# bpf_att.net
KiCad netlist of a schematic drawn in EAGLE
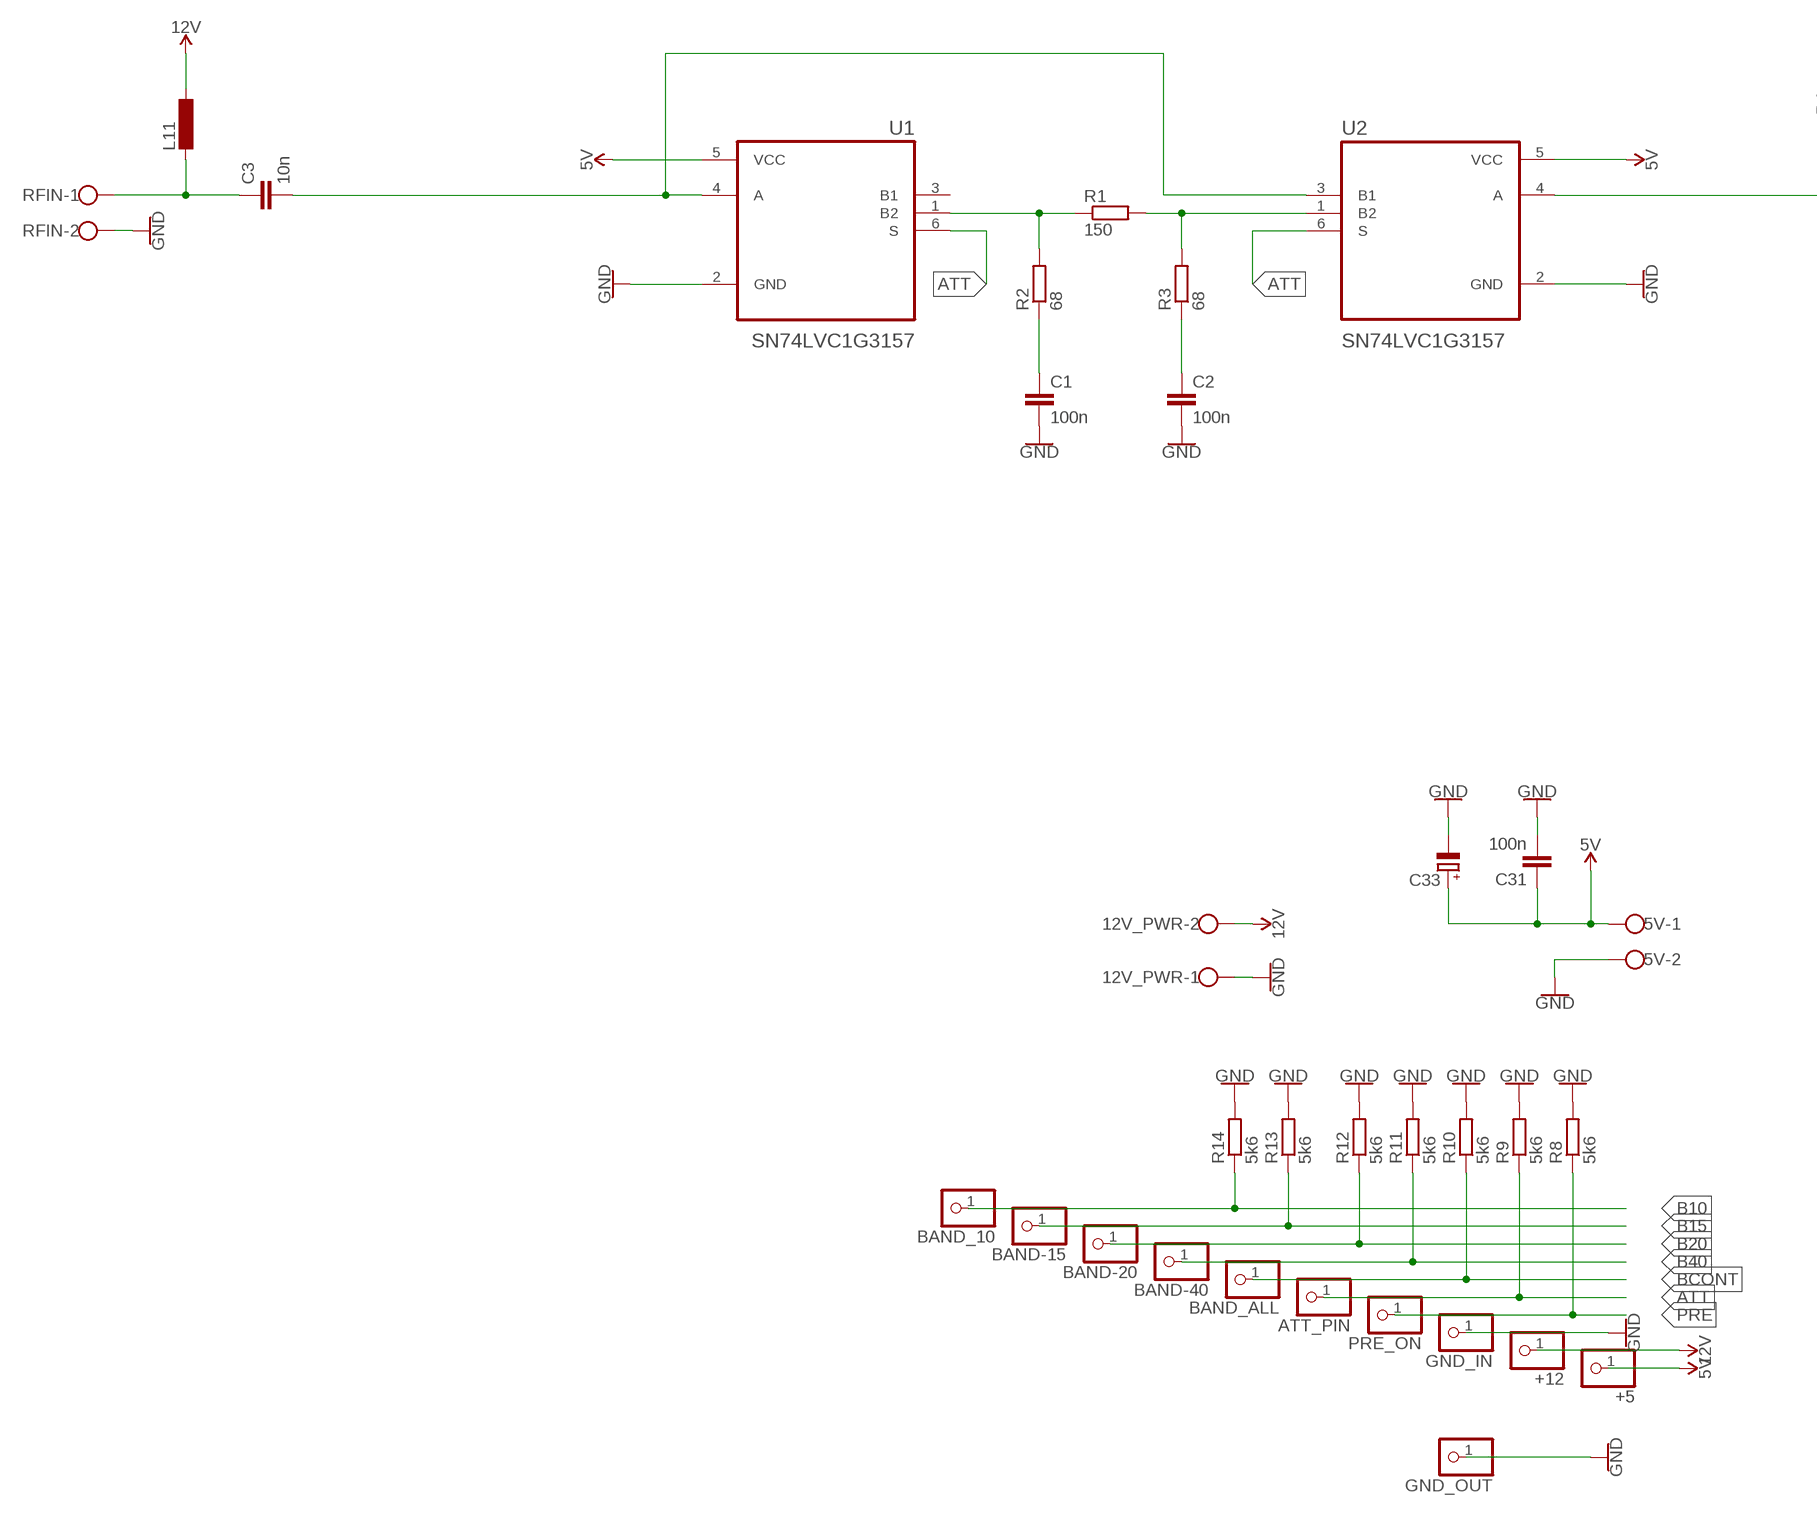
[diagram p0: schematic, sheet 1, part 1 of 2]
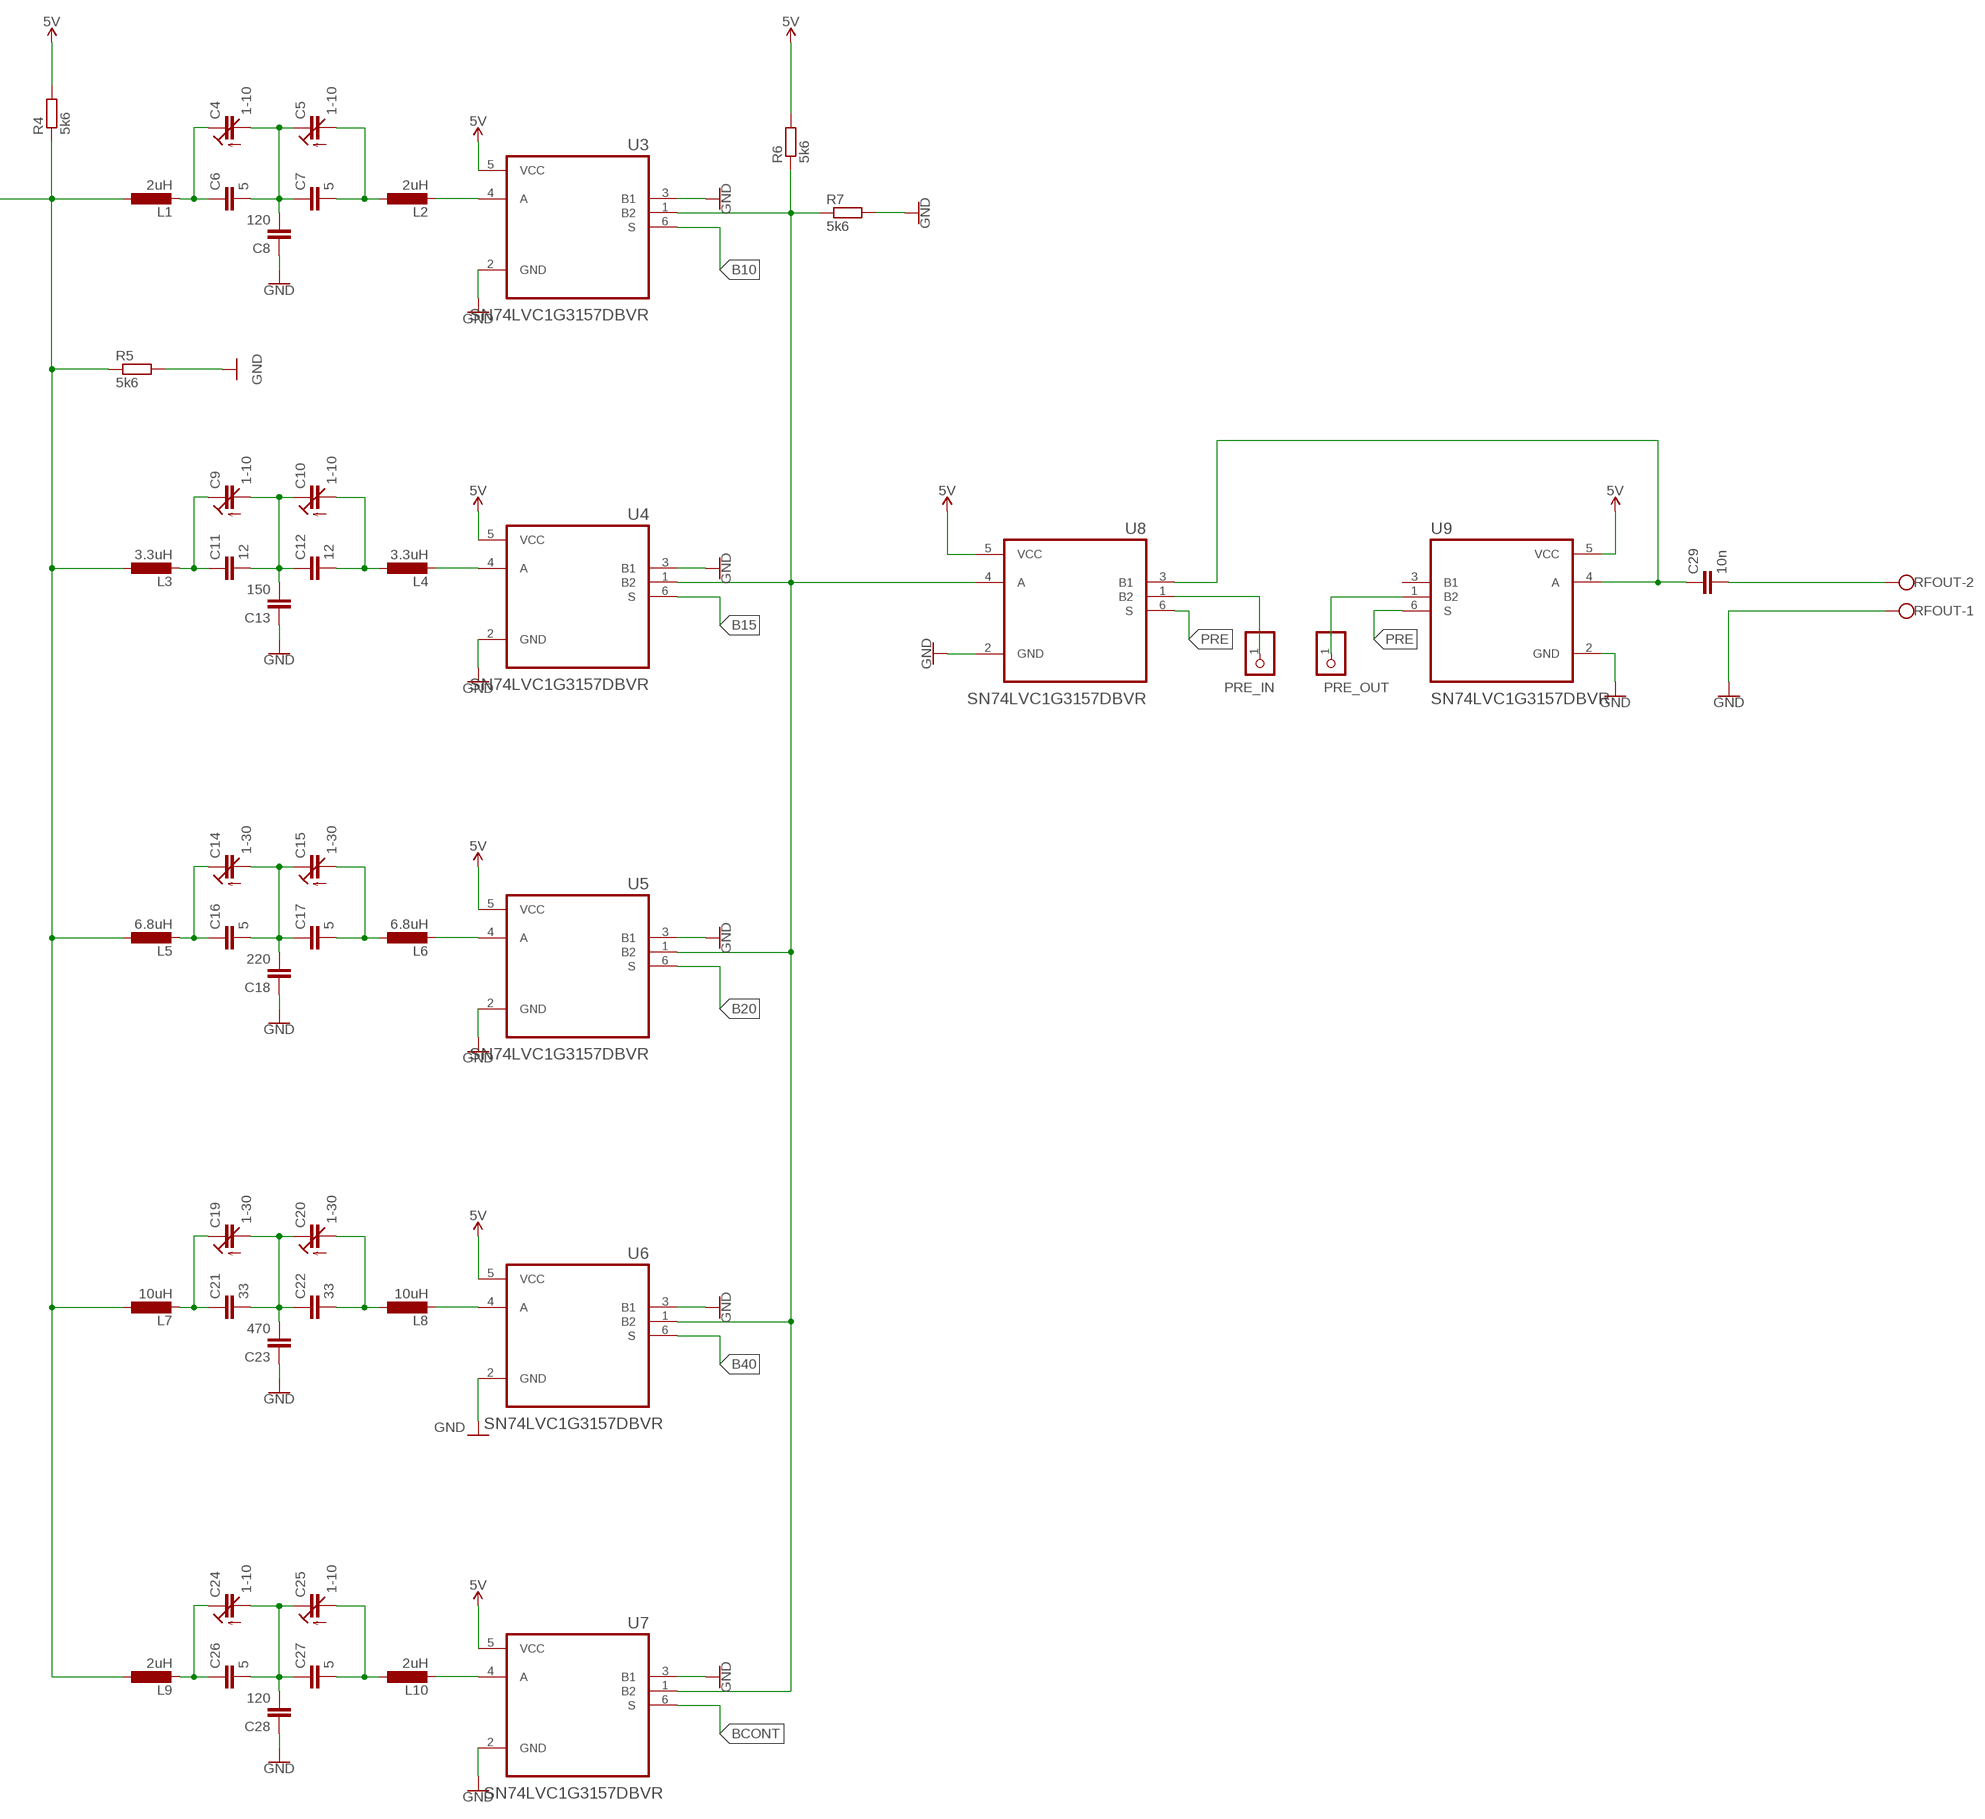
[diagram p1: schematic, sheet 1, part 2 of 2]

(export (version "E")
  (design (tool "Eeschema 10.0.6"))
  (components
    (comp (ref "+5")
      (value "PINHD-1X1")
      (footprint "eagle-import:1X01")
      (libsource (lib "eagle-import") (part "PINHD-1X1"))
    )
    (comp (ref "+12")
      (value "PINHD-1X1")
      (footprint "eagle-import:1X01")
      (libsource (lib "eagle-import") (part "PINHD-1X1"))
    )
    (comp (ref "5V")
      (value "W237-102")
      (footprint "eagle-import:W237-102")
      (fields (field (name "MPN") "237-102"))
      (libsource (lib "eagle-import") (part "W237-102"))
    )
    (comp (ref "12V_PWR")
      (value "W237-102")
      (footprint "eagle-import:W237-102")
      (fields (field (name "MPN") "237-102"))
      (libsource (lib "eagle-import") (part "W237-102"))
    )
    (comp (ref "ATT_PIN")
      (value "PINHD-1X1")
      (footprint "eagle-import:1X01")
      (libsource (lib "eagle-import") (part "PINHD-1X1"))
    )
    (comp (ref "BAND-15")
      (value "PINHD-1X1")
      (footprint "eagle-import:1X01")
      (libsource (lib "eagle-import") (part "PINHD-1X1"))
    )
    (comp (ref "BAND-20")
      (value "PINHD-1X1")
      (footprint "eagle-import:1X01")
      (libsource (lib "eagle-import") (part "PINHD-1X1"))
    )
    (comp (ref "BAND-40")
      (value "PINHD-1X1")
      (footprint "eagle-import:1X01")
      (libsource (lib "eagle-import") (part "PINHD-1X1"))
    )
    (comp (ref "BAND_10")
      (value "PINHD-1X1")
      (footprint "eagle-import:1X01")
      (libsource (lib "eagle-import") (part "PINHD-1X1"))
    )
    (comp (ref "BAND_ALL")
      (value "PINHD-1X1")
      (footprint "eagle-import:1X01")
      (libsource (lib "eagle-import") (part "PINHD-1X1"))
    )
    (comp (ref "C1")
      (value "100n")
      (footprint "eagle-import:C1206")
      (libsource (lib "eagle-import") (part "C-EUC1206"))
    )
    (comp (ref "C2")
      (value "100n")
      (footprint "eagle-import:C1206")
      (libsource (lib "eagle-import") (part "C-EUC1206"))
    )
    (comp (ref "C3")
      (value "10n")
      (footprint "eagle-import:C1206K")
      (libsource (lib "eagle-import") (part "C-EUC1206K"))
    )
    (comp (ref "C4")
      (value "1-10")
      (footprint "eagle-import:CTRIM3050.504")
      (libsource (lib "eagle-import") (part "C-TRIMM3050.504"))
    )
    (comp (ref "C5")
      (value "1-10")
      (footprint "eagle-import:CTRIM3050.504")
      (libsource (lib "eagle-import") (part "C-TRIMM3050.504"))
    )
    (comp (ref "C6")
      (value "5")
      (footprint "eagle-import:C1206K")
      (libsource (lib "eagle-import") (part "C-EUC1206K"))
    )
    (comp (ref "C7")
      (value "5")
      (footprint "eagle-import:C1206K")
      (libsource (lib "eagle-import") (part "C-EUC1206K"))
    )
    (comp (ref "C8")
      (value "120")
      (footprint "eagle-import:C1206K")
      (libsource (lib "eagle-import") (part "C-EUC1206K"))
    )
    (comp (ref "C9")
      (value "1-10")
      (footprint "eagle-import:CTRIM3050.504")
      (libsource (lib "eagle-import") (part "C-TRIMM3050.504"))
    )
    (comp (ref "C10")
      (value "1-10")
      (footprint "eagle-import:CTRIM3050.504")
      (libsource (lib "eagle-import") (part "C-TRIMM3050.504"))
    )
    (comp (ref "C11")
      (value "12")
      (footprint "eagle-import:C1206K")
      (libsource (lib "eagle-import") (part "C-EUC1206K"))
    )
    (comp (ref "C12")
      (value "12")
      (footprint "eagle-import:C1206K")
      (libsource (lib "eagle-import") (part "C-EUC1206K"))
    )
    (comp (ref "C13")
      (value "150")
      (footprint "eagle-import:C1206K")
      (libsource (lib "eagle-import") (part "C-EUC1206K"))
    )
    (comp (ref "C14")
      (value "1-30")
      (footprint "eagle-import:CTRIM3050.504")
      (libsource (lib "eagle-import") (part "C-TRIMM3050.504"))
    )
    (comp (ref "C15")
      (value "1-30")
      (footprint "eagle-import:CTRIM3050.504")
      (libsource (lib "eagle-import") (part "C-TRIMM3050.504"))
    )
    (comp (ref "C16")
      (value "5")
      (footprint "eagle-import:C1206K")
      (libsource (lib "eagle-import") (part "C-EUC1206K"))
    )
    (comp (ref "C17")
      (value "5")
      (footprint "eagle-import:C1206K")
      (libsource (lib "eagle-import") (part "C-EUC1206K"))
    )
    (comp (ref "C18")
      (value "220")
      (footprint "eagle-import:C1206K")
      (libsource (lib "eagle-import") (part "C-EUC1206K"))
    )
    (comp (ref "C19")
      (value "1-30")
      (footprint "eagle-import:CTRIM3050.504")
      (libsource (lib "eagle-import") (part "C-TRIMM3050.504"))
    )
    (comp (ref "C20")
      (value "1-30")
      (footprint "eagle-import:CTRIM3050.504")
      (libsource (lib "eagle-import") (part "C-TRIMM3050.504"))
    )
    (comp (ref "C21")
      (value "33")
      (footprint "eagle-import:C1206K")
      (libsource (lib "eagle-import") (part "C-EUC1206K"))
    )
    (comp (ref "C22")
      (value "33")
      (footprint "eagle-import:C1206K")
      (libsource (lib "eagle-import") (part "C-EUC1206K"))
    )
    (comp (ref "C23")
      (value "470")
      (footprint "eagle-import:C1206K")
      (libsource (lib "eagle-import") (part "C-EUC1206K"))
    )
    (comp (ref "C24")
      (value "1-10")
      (footprint "eagle-import:CTRIM3050.504")
      (libsource (lib "eagle-import") (part "C-TRIMM3050.504"))
    )
    (comp (ref "C25")
      (value "1-10")
      (footprint "eagle-import:CTRIM3050.504")
      (libsource (lib "eagle-import") (part "C-TRIMM3050.504"))
    )
    (comp (ref "C26")
      (value "5")
      (footprint "eagle-import:C1206K")
      (libsource (lib "eagle-import") (part "C-EUC1206K"))
    )
    (comp (ref "C27")
      (value "5")
      (footprint "eagle-import:C1206K")
      (libsource (lib "eagle-import") (part "C-EUC1206K"))
    )
    (comp (ref "C28")
      (value "120")
      (footprint "eagle-import:C1206K")
      (libsource (lib "eagle-import") (part "C-EUC1206K"))
    )
    (comp (ref "C29")
      (value "10n")
      (footprint "eagle-import:C1206K")
      (libsource (lib "eagle-import") (part "C-EUC1206K"))
    )
    (comp (ref "C31")
      (value "100n")
      (footprint "eagle-import:C1206")
      (libsource (lib "eagle-import") (part "C-EUC1206"))
    )
    (comp (ref "C33")
      (value "CPOL-EUSMCD")
      (footprint "eagle-import:SMC_D")
      (libsource (lib "eagle-import") (part "CPOL-EUSMCD"))
    )
    (comp (ref "GND_IN")
      (value "PINHD-1X1")
      (footprint "eagle-import:1X01")
      (libsource (lib "eagle-import") (part "PINHD-1X1"))
    )
    (comp (ref "GND_OUT")
      (value "PINHD-1X1")
      (footprint "eagle-import:1X01")
      (libsource (lib "eagle-import") (part "PINHD-1X1"))
    )
    (comp (ref "L1")
      (value "2uH")
      (footprint "eagle-import:0204_7")
      (libsource (lib "eagle-import") (part "L-EU0204/7"))
    )
    (comp (ref "L2")
      (value "2uH")
      (footprint "eagle-import:0204_7")
      (libsource (lib "eagle-import") (part "L-EU0204/7"))
    )
    (comp (ref "L3")
      (value "3.3uH")
      (footprint "eagle-import:0204_7")
      (libsource (lib "eagle-import") (part "L-EU0204/7"))
    )
    (comp (ref "L4")
      (value "3.3uH")
      (footprint "eagle-import:0204_7")
      (libsource (lib "eagle-import") (part "L-EU0204/7"))
    )
    (comp (ref "L5")
      (value "6.8uH")
      (footprint "eagle-import:0204_7")
      (libsource (lib "eagle-import") (part "L-EU0204/7"))
    )
    (comp (ref "L6")
      (value "6.8uH")
      (footprint "eagle-import:0204_7")
      (libsource (lib "eagle-import") (part "L-EU0204/7"))
    )
    (comp (ref "L7")
      (value "10uH")
      (footprint "eagle-import:0204_7")
      (libsource (lib "eagle-import") (part "L-EU0204/7"))
    )
    (comp (ref "L8")
      (value "10uH")
      (footprint "eagle-import:0204_7")
      (libsource (lib "eagle-import") (part "L-EU0204/7"))
    )
    (comp (ref "L9")
      (value "2uH")
      (footprint "eagle-import:0204_7")
      (libsource (lib "eagle-import") (part "L-EU0204/7"))
    )
    (comp (ref "L10")
      (value "2uH")
      (footprint "eagle-import:0204_7")
      (libsource (lib "eagle-import") (part "L-EU0204/7"))
    )
    (comp (ref "L11")
      (value "L-EU0204/7")
      (footprint "eagle-import:0204_7")
      (libsource (lib "eagle-import") (part "L-EU0204/7"))
    )
    (comp (ref "PRE_IN")
      (value "PINHD-1X1")
      (footprint "eagle-import:1X01")
      (libsource (lib "eagle-import") (part "PINHD-1X1"))
    )
    (comp (ref "PRE_ON")
      (value "PINHD-1X1")
      (footprint "eagle-import:1X01")
      (libsource (lib "eagle-import") (part "PINHD-1X1"))
    )
    (comp (ref "PRE_OUT")
      (value "PINHD-1X1")
      (footprint "eagle-import:1X01")
      (libsource (lib "eagle-import") (part "PINHD-1X1"))
    )
    (comp (ref "R1")
      (value "150")
      (footprint "eagle-import:R1206")
      (libsource (lib "eagle-import") (part "R-EU_R1206"))
    )
    (comp (ref "R2")
      (value "68")
      (footprint "eagle-import:R1206")
      (libsource (lib "eagle-import") (part "R-EU_R1206"))
    )
    (comp (ref "R3")
      (value "68")
      (footprint "eagle-import:R1206")
      (libsource (lib "eagle-import") (part "R-EU_R1206"))
    )
    (comp (ref "R4")
      (value "5k6")
      (footprint "eagle-import:R1206")
      (libsource (lib "eagle-import") (part "R-EU_R1206"))
    )
    (comp (ref "R5")
      (value "5k6")
      (footprint "eagle-import:R1206")
      (libsource (lib "eagle-import") (part "R-EU_R1206"))
    )
    (comp (ref "R6")
      (value "5k6")
      (footprint "eagle-import:R0805")
      (libsource (lib "eagle-import") (part "R-EU_R0805"))
    )
    (comp (ref "R7")
      (value "5k6")
      (footprint "eagle-import:R0805")
      (libsource (lib "eagle-import") (part "R-EU_R0805"))
    )
    (comp (ref "R8")
      (value "5k6")
      (footprint "eagle-import:R1206")
      (libsource (lib "eagle-import") (part "R-EU_R1206"))
    )
    (comp (ref "R9")
      (value "5k6")
      (footprint "eagle-import:R1206")
      (libsource (lib "eagle-import") (part "R-EU_R1206"))
    )
    (comp (ref "R10")
      (value "5k6")
      (footprint "eagle-import:R0805")
      (libsource (lib "eagle-import") (part "R-EU_R0805"))
    )
    (comp (ref "R11")
      (value "5k6")
      (footprint "eagle-import:R0805")
      (libsource (lib "eagle-import") (part "R-EU_R0805"))
    )
    (comp (ref "R12")
      (value "5k6")
      (footprint "eagle-import:R0805")
      (libsource (lib "eagle-import") (part "R-EU_R0805"))
    )
    (comp (ref "R13")
      (value "5k6")
      (footprint "eagle-import:R0805")
      (libsource (lib "eagle-import") (part "R-EU_R0805"))
    )
    (comp (ref "R14")
      (value "5k6")
      (footprint "eagle-import:R0805")
      (libsource (lib "eagle-import") (part "R-EU_R0805"))
    )
    (comp (ref "RFIN")
      (value "W237-102")
      (footprint "eagle-import:W237-102")
      (fields (field (name "MPN") "237-102"))
      (libsource (lib "eagle-import") (part "W237-102"))
    )
    (comp (ref "RFOUT")
      (value "W237-102")
      (footprint "eagle-import:W237-102")
      (fields (field (name "MPN") "237-102"))
      (libsource (lib "eagle-import") (part "W237-102"))
    )
    (comp (ref "U1")
      (value "SN74LVC1G3157")
      (footprint "eagle-import:SOT95P280X145-6N")
      (fields (field (name "MF") "Texas Instruments") (field (name "MP") "SN74LVC1G3157DBVR"))
      (libsource (lib "eagle-import") (part "SN74LVC1G3157DBVR"))
    )
    (comp (ref "U2")
      (value "SN74LVC1G3157")
      (footprint "eagle-import:SOT95P280X145-6N")
      (fields (field (name "MF") "Texas Instruments") (field (name "MP") "SN74LVC1G3157DBVR"))
      (libsource (lib "eagle-import") (part "SN74LVC1G3157DBVR"))
    )
    (comp (ref "U3")
      (value "SN74LVC1G3157DBVR")
      (footprint "eagle-import:SOT95P280X145-6N")
      (fields (field (name "MF") "Texas Instruments"))
      (libsource (lib "eagle-import") (part "SN74LVC1G3157DBVR"))
    )
    (comp (ref "U4")
      (value "SN74LVC1G3157DBVR")
      (footprint "eagle-import:SOT95P280X145-6N")
      (fields (field (name "MF") "Texas Instruments"))
      (libsource (lib "eagle-import") (part "SN74LVC1G3157DBVR"))
    )
    (comp (ref "U5")
      (value "SN74LVC1G3157DBVR")
      (footprint "eagle-import:SOT95P280X145-6N")
      (fields (field (name "MF") "Texas Instruments"))
      (libsource (lib "eagle-import") (part "SN74LVC1G3157DBVR"))
    )
    (comp (ref "U6")
      (value "SN74LVC1G3157DBVR")
      (footprint "eagle-import:SOT95P280X145-6N")
      (fields (field (name "MF") "Texas Instruments"))
      (libsource (lib "eagle-import") (part "SN74LVC1G3157DBVR"))
    )
    (comp (ref "U7")
      (value "SN74LVC1G3157DBVR")
      (footprint "eagle-import:SOT95P280X145-6N")
      (fields (field (name "MF") "Texas Instruments"))
      (libsource (lib "eagle-import") (part "SN74LVC1G3157DBVR"))
    )
    (comp (ref "U8")
      (value "SN74LVC1G3157DBVR")
      (footprint "eagle-import:SOT95P280X145-6N")
      (fields (field (name "MF") "Texas Instruments"))
      (libsource (lib "eagle-import") (part "SN74LVC1G3157DBVR"))
    )
    (comp (ref "U9")
      (value "SN74LVC1G3157DBVR")
      (footprint "eagle-import:SOT95P280X145-6N")
      (fields (field (name "MF") "Texas Instruments"))
      (libsource (lib "eagle-import") (part "SN74LVC1G3157DBVR"))
    )
  )
  (nets
    (net (code "1") (name "5V") (class "Default")
      (node (ref "+5") (pin "1") (pinfunction "1_1") (pintype "passive"))
      (node (ref "5V") (pin "1") (pinfunction "KL_1") (pintype "passive"))
      (node (ref "C31") (pin "1") (pinfunction "1_1") (pintype "passive"))
      (node (ref "C33") (pin "+") (pinfunction "+_+") (pintype "passive"))
      (node (ref "R4") (pin "2") (pinfunction "2_2") (pintype "passive"))
      (node (ref "R6") (pin "2") (pinfunction "2_2") (pintype "passive"))
      (node (ref "U1") (pin "5") (pinfunction "VCC_5") (pintype "power_in"))
      (node (ref "U2") (pin "5") (pinfunction "VCC_5") (pintype "power_in"))
      (node (ref "U3") (pin "5") (pinfunction "VCC_5") (pintype "power_in"))
      (node (ref "U4") (pin "5") (pinfunction "VCC_5") (pintype "power_in"))
      (node (ref "U5") (pin "5") (pinfunction "VCC_5") (pintype "power_in"))
      (node (ref "U6") (pin "5") (pinfunction "VCC_5") (pintype "power_in"))
      (node (ref "U7") (pin "5") (pinfunction "VCC_5") (pintype "power_in"))
      (node (ref "U8") (pin "5") (pinfunction "VCC_5") (pintype "power_in"))
      (node (ref "U9") (pin "5") (pinfunction "VCC_5") (pintype "power_in"))
    )
    (net (code "2") (name "12V") (class "Default")
      (node (ref "+12") (pin "1") (pinfunction "1_1") (pintype "passive"))
      (node (ref "12V_PWR") (pin "2") (pinfunction "KL_2") (pintype "passive"))
      (node (ref "L11") (pin "1") (pinfunction "1_1") (pintype "passive"))
    )
    (net (code "3") (name "ATT") (class "Default")
      (node (ref "ATT_PIN") (pin "1") (pinfunction "1_1") (pintype "passive"))
      (node (ref "R9") (pin "1") (pinfunction "1_1") (pintype "passive"))
      (node (ref "U1") (pin "6") (pinfunction "S_6") (pintype "input"))
      (node (ref "U2") (pin "6") (pinfunction "S_6") (pintype "input"))
    )
    (net (code "4") (name "B10") (class "Default")
      (node (ref "BAND_10") (pin "1") (pinfunction "1_1") (pintype "passive"))
      (node (ref "R14") (pin "1") (pinfunction "1_1") (pintype "passive"))
      (node (ref "U3") (pin "6") (pinfunction "S_6") (pintype "input"))
    )
    (net (code "5") (name "B15") (class "Default")
      (node (ref "BAND-15") (pin "1") (pinfunction "1_1") (pintype "passive"))
      (node (ref "R13") (pin "1") (pinfunction "1_1") (pintype "passive"))
      (node (ref "U4") (pin "6") (pinfunction "S_6") (pintype "input"))
    )
    (net (code "6") (name "B20") (class "Default")
      (node (ref "BAND-20") (pin "1") (pinfunction "1_1") (pintype "passive"))
      (node (ref "R12") (pin "1") (pinfunction "1_1") (pintype "passive"))
      (node (ref "U5") (pin "6") (pinfunction "S_6") (pintype "input"))
    )
    (net (code "7") (name "B40") (class "Default")
      (node (ref "BAND-40") (pin "1") (pinfunction "1_1") (pintype "passive"))
      (node (ref "R11") (pin "1") (pinfunction "1_1") (pintype "passive"))
      (node (ref "U6") (pin "6") (pinfunction "S_6") (pintype "input"))
    )
    (net (code "8") (name "BCONT") (class "Default")
      (node (ref "BAND_ALL") (pin "1") (pinfunction "1_1") (pintype "passive"))
      (node (ref "R10") (pin "1") (pinfunction "1_1") (pintype "passive"))
      (node (ref "U7") (pin "6") (pinfunction "S_6") (pintype "input"))
    )
    (net (code "9") (name "GND") (class "Default")
      (node (ref "12V_PWR") (pin "1") (pinfunction "KL_1") (pintype "passive"))
      (node (ref "5V") (pin "2") (pinfunction "KL_2") (pintype "passive"))
      (node (ref "C1") (pin "2") (pinfunction "2_2") (pintype "passive"))
      (node (ref "C13") (pin "1") (pinfunction "1_1") (pintype "passive"))
      (node (ref "C18") (pin "1") (pinfunction "1_1") (pintype "passive"))
      (node (ref "C2") (pin "2") (pinfunction "2_2") (pintype "passive"))
      (node (ref "C23") (pin "1") (pinfunction "1_1") (pintype "passive"))
      (node (ref "C28") (pin "1") (pinfunction "1_1") (pintype "passive"))
      (node (ref "C31") (pin "2") (pinfunction "2_2") (pintype "passive"))
      (node (ref "C33") (pin "-") (pinfunction "-_-") (pintype "passive"))
      (node (ref "C8") (pin "1") (pinfunction "1_1") (pintype "passive"))
      (node (ref "GND_IN") (pin "1") (pinfunction "1_1") (pintype "passive"))
      (node (ref "GND_OUT") (pin "1") (pinfunction "1_1") (pintype "passive"))
      (node (ref "R10") (pin "2") (pinfunction "2_2") (pintype "passive"))
      (node (ref "R11") (pin "2") (pinfunction "2_2") (pintype "passive"))
      (node (ref "R12") (pin "2") (pinfunction "2_2") (pintype "passive"))
      (node (ref "R13") (pin "2") (pinfunction "2_2") (pintype "passive"))
      (node (ref "R14") (pin "2") (pinfunction "2_2") (pintype "passive"))
      (node (ref "R5") (pin "2") (pinfunction "2_2") (pintype "passive"))
      (node (ref "R7") (pin "2") (pinfunction "2_2") (pintype "passive"))
      (node (ref "R8") (pin "2") (pinfunction "2_2") (pintype "passive"))
      (node (ref "R9") (pin "2") (pinfunction "2_2") (pintype "passive"))
      (node (ref "RFIN") (pin "2") (pinfunction "KL_2") (pintype "passive"))
      (node (ref "RFOUT") (pin "1") (pinfunction "KL_1") (pintype "passive"))
      (node (ref "U1") (pin "2") (pinfunction "GND_2") (pintype "power_in"))
      (node (ref "U2") (pin "2") (pinfunction "GND_2") (pintype "power_in"))
      (node (ref "U3") (pin "2") (pinfunction "GND_2") (pintype "power_in"))
      (node (ref "U3") (pin "3") (pinfunction "B1_3") (pintype "input"))
      (node (ref "U4") (pin "2") (pinfunction "GND_2") (pintype "power_in"))
      (node (ref "U4") (pin "3") (pinfunction "B1_3") (pintype "input"))
      (node (ref "U5") (pin "2") (pinfunction "GND_2") (pintype "power_in"))
      (node (ref "U5") (pin "3") (pinfunction "B1_3") (pintype "input"))
      (node (ref "U6") (pin "2") (pinfunction "GND_2") (pintype "power_in"))
      (node (ref "U6") (pin "3") (pinfunction "B1_3") (pintype "input"))
      (node (ref "U7") (pin "2") (pinfunction "GND_2") (pintype "power_in"))
      (node (ref "U7") (pin "3") (pinfunction "B1_3") (pintype "input"))
      (node (ref "U8") (pin "2") (pinfunction "GND_2") (pintype "power_in"))
      (node (ref "U9") (pin "2") (pinfunction "GND_2") (pintype "power_in"))
    )
    (net (code "10") (name "Net-(C1-Pad1)") (class "Default")
      (node (ref "C1") (pin "1") (pinfunction "1_1") (pintype "passive"))
      (node (ref "R2") (pin "1") (pinfunction "1_1") (pintype "passive"))
    )
    (net (code "11") (name "Net-(C2-Pad1)") (class "Default")
      (node (ref "C2") (pin "1") (pinfunction "1_1") (pintype "passive"))
      (node (ref "R3") (pin "1") (pinfunction "1_1") (pintype "passive"))
    )
    (net (code "12") (name "Net-(C4-A)") (class "Default")
      (node (ref "C4") (pin "2") (pinfunction "A_2") (pintype "passive"))
      (node (ref "C5") (pin "1") (pinfunction "E_1") (pintype "passive"))
      (node (ref "C6") (pin "2") (pinfunction "2_2") (pintype "passive"))
      (node (ref "C7") (pin "1") (pinfunction "1_1") (pintype "passive"))
      (node (ref "C8") (pin "2") (pinfunction "2_2") (pintype "passive"))
    )
    (net (code "13") (name "Net-(C4-E)") (class "Default")
      (node (ref "C4") (pin "1") (pinfunction "E_1") (pintype "passive"))
      (node (ref "C6") (pin "1") (pinfunction "1_1") (pintype "passive"))
      (node (ref "L1") (pin "2") (pinfunction "2_2") (pintype "passive"))
    )
    (net (code "14") (name "Net-(C5-A)") (class "Default")
      (node (ref "C5") (pin "2") (pinfunction "A_2") (pintype "passive"))
      (node (ref "C7") (pin "2") (pinfunction "2_2") (pintype "passive"))
      (node (ref "L2") (pin "1") (pinfunction "1_1") (pintype "passive"))
    )
    (net (code "15") (name "Net-(C9-E)") (class "Default")
      (node (ref "C11") (pin "1") (pinfunction "1_1") (pintype "passive"))
      (node (ref "C9") (pin "1") (pinfunction "E_1") (pintype "passive"))
      (node (ref "L3") (pin "2") (pinfunction "2_2") (pintype "passive"))
    )
    (net (code "16") (name "Net-(C10-A)") (class "Default")
      (node (ref "C10") (pin "2") (pinfunction "A_2") (pintype "passive"))
      (node (ref "C12") (pin "2") (pinfunction "2_2") (pintype "passive"))
      (node (ref "L4") (pin "1") (pinfunction "1_1") (pintype "passive"))
    )
    (net (code "17") (name "Net-(C10-E)") (class "Default")
      (node (ref "C10") (pin "1") (pinfunction "E_1") (pintype "passive"))
      (node (ref "C11") (pin "2") (pinfunction "2_2") (pintype "passive"))
      (node (ref "C12") (pin "1") (pinfunction "1_1") (pintype "passive"))
      (node (ref "C13") (pin "2") (pinfunction "2_2") (pintype "passive"))
      (node (ref "C9") (pin "2") (pinfunction "A_2") (pintype "passive"))
    )
    (net (code "18") (name "Net-(C14-A)") (class "Default")
      (node (ref "C14") (pin "2") (pinfunction "A_2") (pintype "passive"))
      (node (ref "C15") (pin "1") (pinfunction "E_1") (pintype "passive"))
      (node (ref "C16") (pin "2") (pinfunction "2_2") (pintype "passive"))
      (node (ref "C17") (pin "1") (pinfunction "1_1") (pintype "passive"))
      (node (ref "C18") (pin "2") (pinfunction "2_2") (pintype "passive"))
    )
    (net (code "19") (name "Net-(C14-E)") (class "Default")
      (node (ref "C14") (pin "1") (pinfunction "E_1") (pintype "passive"))
      (node (ref "C16") (pin "1") (pinfunction "1_1") (pintype "passive"))
      (node (ref "L5") (pin "2") (pinfunction "2_2") (pintype "passive"))
    )
    (net (code "20") (name "Net-(C15-A)") (class "Default")
      (node (ref "C15") (pin "2") (pinfunction "A_2") (pintype "passive"))
      (node (ref "C17") (pin "2") (pinfunction "2_2") (pintype "passive"))
      (node (ref "L6") (pin "1") (pinfunction "1_1") (pintype "passive"))
    )
    (net (code "21") (name "Net-(C19-A)") (class "Default")
      (node (ref "C19") (pin "2") (pinfunction "A_2") (pintype "passive"))
      (node (ref "C20") (pin "1") (pinfunction "E_1") (pintype "passive"))
      (node (ref "C21") (pin "2") (pinfunction "2_2") (pintype "passive"))
      (node (ref "C22") (pin "1") (pinfunction "1_1") (pintype "passive"))
      (node (ref "C23") (pin "2") (pinfunction "2_2") (pintype "passive"))
    )
    (net (code "22") (name "Net-(C19-E)") (class "Default")
      (node (ref "C19") (pin "1") (pinfunction "E_1") (pintype "passive"))
      (node (ref "C21") (pin "1") (pinfunction "1_1") (pintype "passive"))
      (node (ref "L7") (pin "2") (pinfunction "2_2") (pintype "passive"))
    )
    (net (code "23") (name "Net-(C20-A)") (class "Default")
      (node (ref "C20") (pin "2") (pinfunction "A_2") (pintype "passive"))
      (node (ref "C22") (pin "2") (pinfunction "2_2") (pintype "passive"))
      (node (ref "L8") (pin "1") (pinfunction "1_1") (pintype "passive"))
    )
    (net (code "24") (name "Net-(C24-A)") (class "Default")
      (node (ref "C24") (pin "2") (pinfunction "A_2") (pintype "passive"))
      (node (ref "C25") (pin "1") (pinfunction "E_1") (pintype "passive"))
      (node (ref "C26") (pin "2") (pinfunction "2_2") (pintype "passive"))
      (node (ref "C27") (pin "1") (pinfunction "1_1") (pintype "passive"))
      (node (ref "C28") (pin "2") (pinfunction "2_2") (pintype "passive"))
    )
    (net (code "25") (name "Net-(C24-E)") (class "Default")
      (node (ref "C24") (pin "1") (pinfunction "E_1") (pintype "passive"))
      (node (ref "C26") (pin "1") (pinfunction "1_1") (pintype "passive"))
      (node (ref "L9") (pin "2") (pinfunction "2_2") (pintype "passive"))
    )
    (net (code "26") (name "Net-(C25-A)") (class "Default")
      (node (ref "C25") (pin "2") (pinfunction "A_2") (pintype "passive"))
      (node (ref "C27") (pin "2") (pinfunction "2_2") (pintype "passive"))
      (node (ref "L10") (pin "1") (pinfunction "1_1") (pintype "passive"))
    )
    (net (code "27") (name "Net-(RFINA-KL)") (class "Default")
      (node (ref "C3") (pin "1") (pinfunction "1_1") (pintype "passive"))
      (node (ref "L11") (pin "2") (pinfunction "2_2") (pintype "passive"))
      (node (ref "RFIN") (pin "1") (pinfunction "KL_1") (pintype "passive"))
    )
    (net (code "28") (name "Net-(RFOUTB-KL)") (class "Default")
      (node (ref "C29") (pin "2") (pinfunction "2_2") (pintype "passive"))
      (node (ref "RFOUT") (pin "2") (pinfunction "KL_2") (pintype "passive"))
    )
    (net (code "29") (name "Net-(U1-A)") (class "Default")
      (node (ref "C3") (pin "2") (pinfunction "2_2") (pintype "passive"))
      (node (ref "U1") (pin "4") (pinfunction "A_4") (pintype "output"))
      (node (ref "U2") (pin "3") (pinfunction "B1_3") (pintype "input"))
    )
    (net (code "30") (name "Net-(U1-B2)") (class "Default")
      (node (ref "R1") (pin "1") (pinfunction "1_1") (pintype "passive"))
      (node (ref "R2") (pin "2") (pinfunction "2_2") (pintype "passive"))
      (node (ref "U1") (pin "1") (pinfunction "B2_1") (pintype "input"))
    )
    (net (code "31") (name "Net-(U2-A)") (class "Default")
      (node (ref "L1") (pin "1") (pinfunction "1_1") (pintype "passive"))
      (node (ref "L3") (pin "1") (pinfunction "1_1") (pintype "passive"))
      (node (ref "L5") (pin "1") (pinfunction "1_1") (pintype "passive"))
      (node (ref "L7") (pin "1") (pinfunction "1_1") (pintype "passive"))
      (node (ref "L9") (pin "1") (pinfunction "1_1") (pintype "passive"))
      (node (ref "R4") (pin "1") (pinfunction "1_1") (pintype "passive"))
      (node (ref "R5") (pin "1") (pinfunction "1_1") (pintype "passive"))
      (node (ref "U2") (pin "4") (pinfunction "A_4") (pintype "output"))
    )
    (net (code "32") (name "Net-(U2-B2)") (class "Default")
      (node (ref "R1") (pin "2") (pinfunction "2_2") (pintype "passive"))
      (node (ref "R3") (pin "2") (pinfunction "2_2") (pintype "passive"))
      (node (ref "U2") (pin "1") (pinfunction "B2_1") (pintype "input"))
    )
    (net (code "33") (name "Net-(U3-A)") (class "Default")
      (node (ref "L2") (pin "2") (pinfunction "2_2") (pintype "passive"))
      (node (ref "U3") (pin "4") (pinfunction "A_4") (pintype "output"))
    )
    (net (code "34") (name "Net-(U3-B2)") (class "Default")
      (node (ref "R6") (pin "1") (pinfunction "1_1") (pintype "passive"))
      (node (ref "R7") (pin "1") (pinfunction "1_1") (pintype "passive"))
      (node (ref "U3") (pin "1") (pinfunction "B2_1") (pintype "input"))
      (node (ref "U4") (pin "1") (pinfunction "B2_1") (pintype "input"))
      (node (ref "U5") (pin "1") (pinfunction "B2_1") (pintype "input"))
      (node (ref "U6") (pin "1") (pinfunction "B2_1") (pintype "input"))
      (node (ref "U7") (pin "1") (pinfunction "B2_1") (pintype "input"))
      (node (ref "U8") (pin "4") (pinfunction "A_4") (pintype "output"))
    )
    (net (code "35") (name "Net-(U4-A)") (class "Default")
      (node (ref "L4") (pin "2") (pinfunction "2_2") (pintype "passive"))
      (node (ref "U4") (pin "4") (pinfunction "A_4") (pintype "output"))
    )
    (net (code "36") (name "Net-(U5-A)") (class "Default")
      (node (ref "L6") (pin "2") (pinfunction "2_2") (pintype "passive"))
      (node (ref "U5") (pin "4") (pinfunction "A_4") (pintype "output"))
    )
    (net (code "37") (name "Net-(U6-A)") (class "Default")
      (node (ref "L8") (pin "2") (pinfunction "2_2") (pintype "passive"))
      (node (ref "U6") (pin "4") (pinfunction "A_4") (pintype "output"))
    )
    (net (code "38") (name "Net-(U7-A)") (class "Default")
      (node (ref "L10") (pin "2") (pinfunction "2_2") (pintype "passive"))
      (node (ref "U7") (pin "4") (pinfunction "A_4") (pintype "output"))
    )
    (net (code "39") (name "Net-(U8-B1)") (class "Default")
      (node (ref "C29") (pin "1") (pinfunction "1_1") (pintype "passive"))
      (node (ref "U8") (pin "3") (pinfunction "B1_3") (pintype "input"))
      (node (ref "U9") (pin "4") (pinfunction "A_4") (pintype "output"))
    )
    (net (code "40") (name "Net-(U8-B2)") (class "Default")
      (node (ref "PRE_IN") (pin "1") (pinfunction "1_1") (pintype "passive"))
      (node (ref "U8") (pin "1") (pinfunction "B2_1") (pintype "input"))
    )
    (net (code "41") (name "Net-(U9-B2)") (class "Default")
      (node (ref "PRE_OUT") (pin "1") (pinfunction "1_1") (pintype "passive"))
      (node (ref "U9") (pin "1") (pinfunction "B2_1") (pintype "input"))
    )
    (net (code "42") (name "PRE") (class "Default")
      (node (ref "PRE_ON") (pin "1") (pinfunction "1_1") (pintype "passive"))
      (node (ref "R8") (pin "1") (pinfunction "1_1") (pintype "passive"))
      (node (ref "U8") (pin "6") (pinfunction "S_6") (pintype "input"))
      (node (ref "U9") (pin "6") (pinfunction "S_6") (pintype "input"))
    )
    (net (code "43") (name "unconnected-(U1-B1-Pad3)") (class "Default")
      (node (ref "U1") (pin "3") (pinfunction "B1_3") (pintype "input"))
    )
    (net (code "44") (name "unconnected-(U9-B1-Pad3)") (class "Default")
      (node (ref "U9") (pin "3") (pinfunction "B1_3") (pintype "input"))
    )
  )
)
